# Sensores_boia.net
KiCad netlist of a schematic drawn in Altium Designer
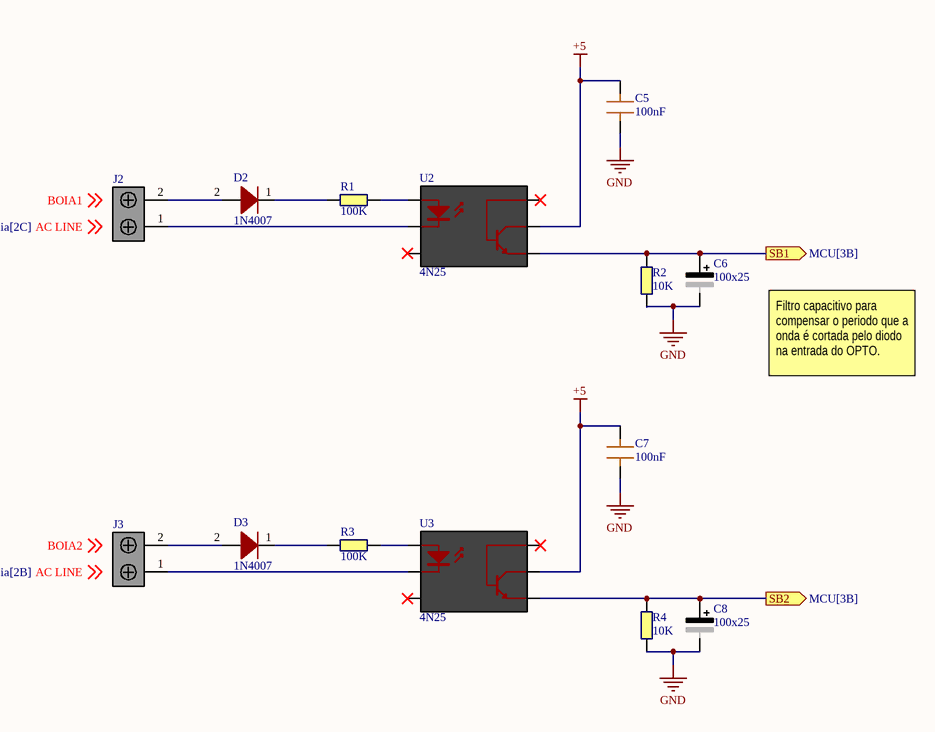
[diagram p0: Sensores boia.SchDoc]

(export (version "E")
  (design (tool "Eeschema 10.0.6"))
  (components
    (comp (ref "C5")
      (value "100nF")
      (footprint "Capacitor 0805")
      (description "Capacitor")
      (fields (field (name "PUBLISHER") "Altium Limited"))
      (libsource (lib "Gerenciador de abastecimento") (part "CAPACITOR"))
    )
    (comp (ref "C6")
      (value "100x25")
      (footprint "CAP 100X25 SMD")
      (description "Polarized Capacitor (Radial)")
      (fields (field (name "PUBLISHER") "Altium Limited"))
      (libsource (lib "Gerenciador de abastecimento") (part "CAPACITOR ELETROLITICO"))
    )
    (comp (ref "C7")
      (value "100nF")
      (footprint "Capacitor 0805")
      (description "Capacitor")
      (fields (field (name "PUBLISHER") "Altium Limited"))
      (libsource (lib "Gerenciador de abastecimento") (part "CAPACITOR"))
    )
    (comp (ref "C8")
      (value "100x25")
      (footprint "CAP 100X25 SMD")
      (description "Polarized Capacitor (Radial)")
      (fields (field (name "PUBLISHER") "Altium Limited"))
      (libsource (lib "Gerenciador de abastecimento") (part "CAPACITOR ELETROLITICO"))
    )
    (comp (ref "D2")
      (value "1N4007")
      (footprint "SOD123")
      (description "Diodo retificador de uso geral.")
      (fields (field (name "PUBLISHER") "Altium Limited"))
      (libsource (lib "Gerenciador de abastecimento") (part "DIODO 1N4007"))
    )
    (comp (ref "D3")
      (value "1N4007")
      (footprint "SOD123")
      (description "Diodo retificador de uso geral.")
      (fields (field (name "PUBLISHER") "Altium Limited"))
      (libsource (lib "Gerenciador de abastecimento") (part "DIODO 1N4007"))
    )
    (comp (ref "J2")
      (value "Conector 2v Phoenix")
      (footprint "Terminal block 5mm 2V")
      (description "Block, Terminal; 6 A; 63 V; 5 mm; 26 to 20 AWG; 2; Screw; Soldering; 1.5 kV")
      (fields
        (field (name "MANUFACTURER") "Phoenix Contact")
        (field (name "MANUFACTURER PART NUMBER") "1725656")
      )
      (libsource (lib "Gerenciador de abastecimento") (part "TERMINAL BLOCK 2V"))
    )
    (comp (ref "J3")
      (value "Conector 2v Phoenix")
      (footprint "Terminal block 5mm 2V")
      (description "Block, Terminal; 6 A; 63 V; 5 mm; 26 to 20 AWG; 2; Screw; Soldering; 1.5 kV")
      (fields
        (field (name "MANUFACTURER") "Phoenix Contact")
        (field (name "MANUFACTURER PART NUMBER") "1725656")
      )
      (libsource (lib "Gerenciador de abastecimento") (part "TERMINAL BLOCK 2V"))
    )
    (comp (ref "R1")
      (value "100K")
      (footprint "RESISTOR 1W 2512")
      (description "Resistor")
      (fields (field (name "PUBLISHER") "Altium Limited"))
      (libsource (lib "Gerenciador de abastecimento") (part "RESISTOR 1W"))
    )
    (comp (ref "R2")
      (value "10K")
      (footprint "RESISTOR 1/4W 0805")
      (description "Resistor")
      (fields (field (name "PUBLISHER") "Altium Limited"))
      (libsource (lib "Gerenciador de abastecimento") (part "RESISTOR 1/4W"))
    )
    (comp (ref "R3")
      (value "100K")
      (footprint "RESISTOR 1W 2512")
      (description "Resistor")
      (fields (field (name "PUBLISHER") "Altium Limited"))
      (libsource (lib "Gerenciador de abastecimento") (part "RESISTOR 1W"))
    )
    (comp (ref "R4")
      (value "10K")
      (footprint "RESISTOR 1/4W 0805")
      (description "Resistor")
      (fields (field (name "PUBLISHER") "Altium Limited"))
      (libsource (lib "Gerenciador de abastecimento") (part "RESISTOR 1/4W"))
    )
    (comp (ref "U2")
      (value "4N25")
      (footprint "4N25")
      (libsource (lib "Gerenciador de abastecimento") (part "4N25"))
    )
    (comp (ref "U3")
      (value "4N25")
      (footprint "4N25")
      (libsource (lib "Gerenciador de abastecimento") (part "4N25"))
    )
  )
  (nets
    (net (code "1") (name "+5") (class "Default")
      (node (ref "C5") (pin "2") (pinfunction "2_2") (pintype "passive"))
      (node (ref "C7") (pin "2") (pinfunction "2_2") (pintype "passive"))
      (node (ref "U2") (pin "5") (pinfunction "C_5") (pintype "passive"))
      (node (ref "U3") (pin "5") (pinfunction "C_5") (pintype "passive"))
    )
    (net (code "2") (name "/SB1") (class "Default")
      (node (ref "C6") (pin "1") (pinfunction "+_1") (pintype "passive"))
      (node (ref "R2") (pin "2") (pinfunction "2_2") (pintype "passive"))
      (node (ref "U2") (pin "6") (pinfunction "E_6") (pintype "passive"))
    )
    (net (code "3") (name "/SB2") (class "Default")
      (node (ref "C8") (pin "1") (pinfunction "+_1") (pintype "passive"))
      (node (ref "R4") (pin "2") (pinfunction "2_2") (pintype "passive"))
      (node (ref "U3") (pin "6") (pinfunction "E_6") (pintype "passive"))
    )
    (net (code "7") (name "GND") (class "Default")
      (node (ref "C5") (pin "1") (pinfunction "1_1") (pintype "passive"))
      (node (ref "C6") (pin "2") (pinfunction "-_2") (pintype "passive"))
      (node (ref "C7") (pin "1") (pinfunction "1_1") (pintype "passive"))
      (node (ref "C8") (pin "2") (pinfunction "-_2") (pintype "passive"))
      (node (ref "R2") (pin "1") (pinfunction "1_1") (pintype "passive"))
      (node (ref "R4") (pin "1") (pinfunction "1_1") (pintype "passive"))
    )
    (net (code "8") (name "Net-(D2-Pad1)") (class "Default")
      (node (ref "D2") (pin "1") (pinfunction "1_1") (pintype "passive"))
      (node (ref "R1") (pin "1") (pinfunction "1_1") (pintype "passive"))
    )
    (net (code "9") (name "Net-(D2-Pad2)") (class "Default")
      (node (ref "D2") (pin "2") (pinfunction "2_2") (pintype "passive"))
      (node (ref "J2") (pin "2") (pinfunction "2_2") (pintype "passive"))
    )
    (net (code "10") (name "Net-(D3-Pad1)") (class "Default")
      (node (ref "D3") (pin "1") (pinfunction "1_1") (pintype "passive"))
      (node (ref "R3") (pin "1") (pinfunction "1_1") (pintype "passive"))
    )
    (net (code "11") (name "Net-(D3-Pad2)") (class "Default")
      (node (ref "D3") (pin "2") (pinfunction "2_2") (pintype "passive"))
      (node (ref "J3") (pin "2") (pinfunction "2_2") (pintype "passive"))
    )
    (net (code "12") (name "Net-(U2-A)") (class "Default")
      (node (ref "R1") (pin "2") (pinfunction "2_2") (pintype "passive"))
      (node (ref "U2") (pin "1") (pinfunction "A_1") (pintype "passive"))
    )
    (net (code "13") (name "Net-(U2-K)") (class "Default")
      (node (ref "J2") (pin "1") (pinfunction "1_1") (pintype "passive"))
      (node (ref "U2") (pin "2") (pinfunction "K_2") (pintype "passive"))
    )
    (net (code "14") (name "Net-(U3-A)") (class "Default")
      (node (ref "R3") (pin "2") (pinfunction "2_2") (pintype "passive"))
      (node (ref "U3") (pin "1") (pinfunction "A_1") (pintype "passive"))
    )
    (net (code "15") (name "Net-(U3-K)") (class "Default")
      (node (ref "J3") (pin "1") (pinfunction "1_1") (pintype "passive"))
      (node (ref "U3") (pin "2") (pinfunction "K_2") (pintype "passive"))
    )
    (net (code "16") (name "unconnected-(U2-B-Pad6)") (class "Default")
      (node (ref "U2") (pin "6") (pinfunction "B_6") (pintype "passive+no_connect"))
    )
    (net (code "17") (name "unconnected-(U2-NC-Pad3)") (class "Default")
      (node (ref "U2") (pin "3") (pinfunction "NC_3") (pintype "passive+no_connect"))
    )
    (net (code "18") (name "unconnected-(U3-B-Pad6)") (class "Default")
      (node (ref "U3") (pin "6") (pinfunction "B_6") (pintype "passive+no_connect"))
    )
    (net (code "19") (name "unconnected-(U3-NC-Pad3)") (class "Default")
      (node (ref "U3") (pin "3") (pinfunction "NC_3") (pintype "passive+no_connect"))
    )
  )
)
